# CATS-EUROC-Storage.net
KiCad netlist of a schematic drawn in Altium Designer
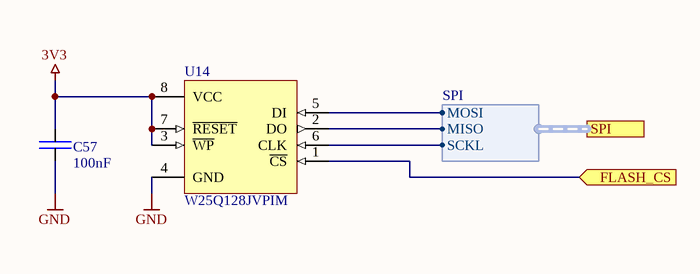
[diagram p0: CATS-EUROC-Storage.SchDoc]

(export (version "E")
  (design (tool "Eeschema 10.0.6"))
  (components
    (comp (ref "C57")
      (value "100nF")
      (footprint "SMD Keramikkondensator 0402")
      (description "SMD Ceramic Capacitor E6")
      (libsource (lib "CATS-EUROC") (part "E6 - 100nF"))
    )
    (comp (ref "U14")
      (value "W25Q128JVPIM")
      (footprint "SMD IC WSON-8 (6x5)")
      (description "3V 128M-BIT\r\nSERIAL FLASH MEMORY WITH\r\nDUAL/QUAD SPI & QPI & DTR")
      (libsource (lib "Digital") (part "W25Q128JVPIM"))
    )
  )
  (nets
    (net (code "2") (name "/FLASH_CS") (class "Default")
      (node (ref "U14") (pin "1") (pinfunction "~{CS}_1") (pintype "input"))
    )
    (net (code "3") (name "/MISO") (class "Default")
      (node (ref "U14") (pin "2") (pinfunction "DO_2") (pintype "output"))
    )
    (net (code "4") (name "/MOSI") (class "Default")
      (node (ref "U14") (pin "5") (pinfunction "DI_5") (pintype "input"))
    )
    (net (code "5") (name "/SCKL") (class "Default")
      (node (ref "U14") (pin "6") (pinfunction "CLK_6") (pintype "input"))
    )
    (net (code "7") (name "3V3") (class "Default")
      (node (ref "C57") (pin "2") (pinfunction "2_2") (pintype "passive"))
      (node (ref "U14") (pin "3") (pinfunction "~{WP}_3") (pintype "input"))
      (node (ref "U14") (pin "7") (pinfunction "~{RESET}_7") (pintype "input"))
      (node (ref "U14") (pin "8") (pinfunction "VCC_8") (pintype "power_in"))
    )
    (net (code "8") (name "GND") (class "Default")
      (node (ref "C57") (pin "1") (pinfunction "1_1") (pintype "passive"))
      (node (ref "U14") (pin "4") (pinfunction "GND_4") (pintype "power_in"))
    )
  )
)
